# 30EC14-43EC14.net
KiCad netlist of a schematic drawn in EAGLE
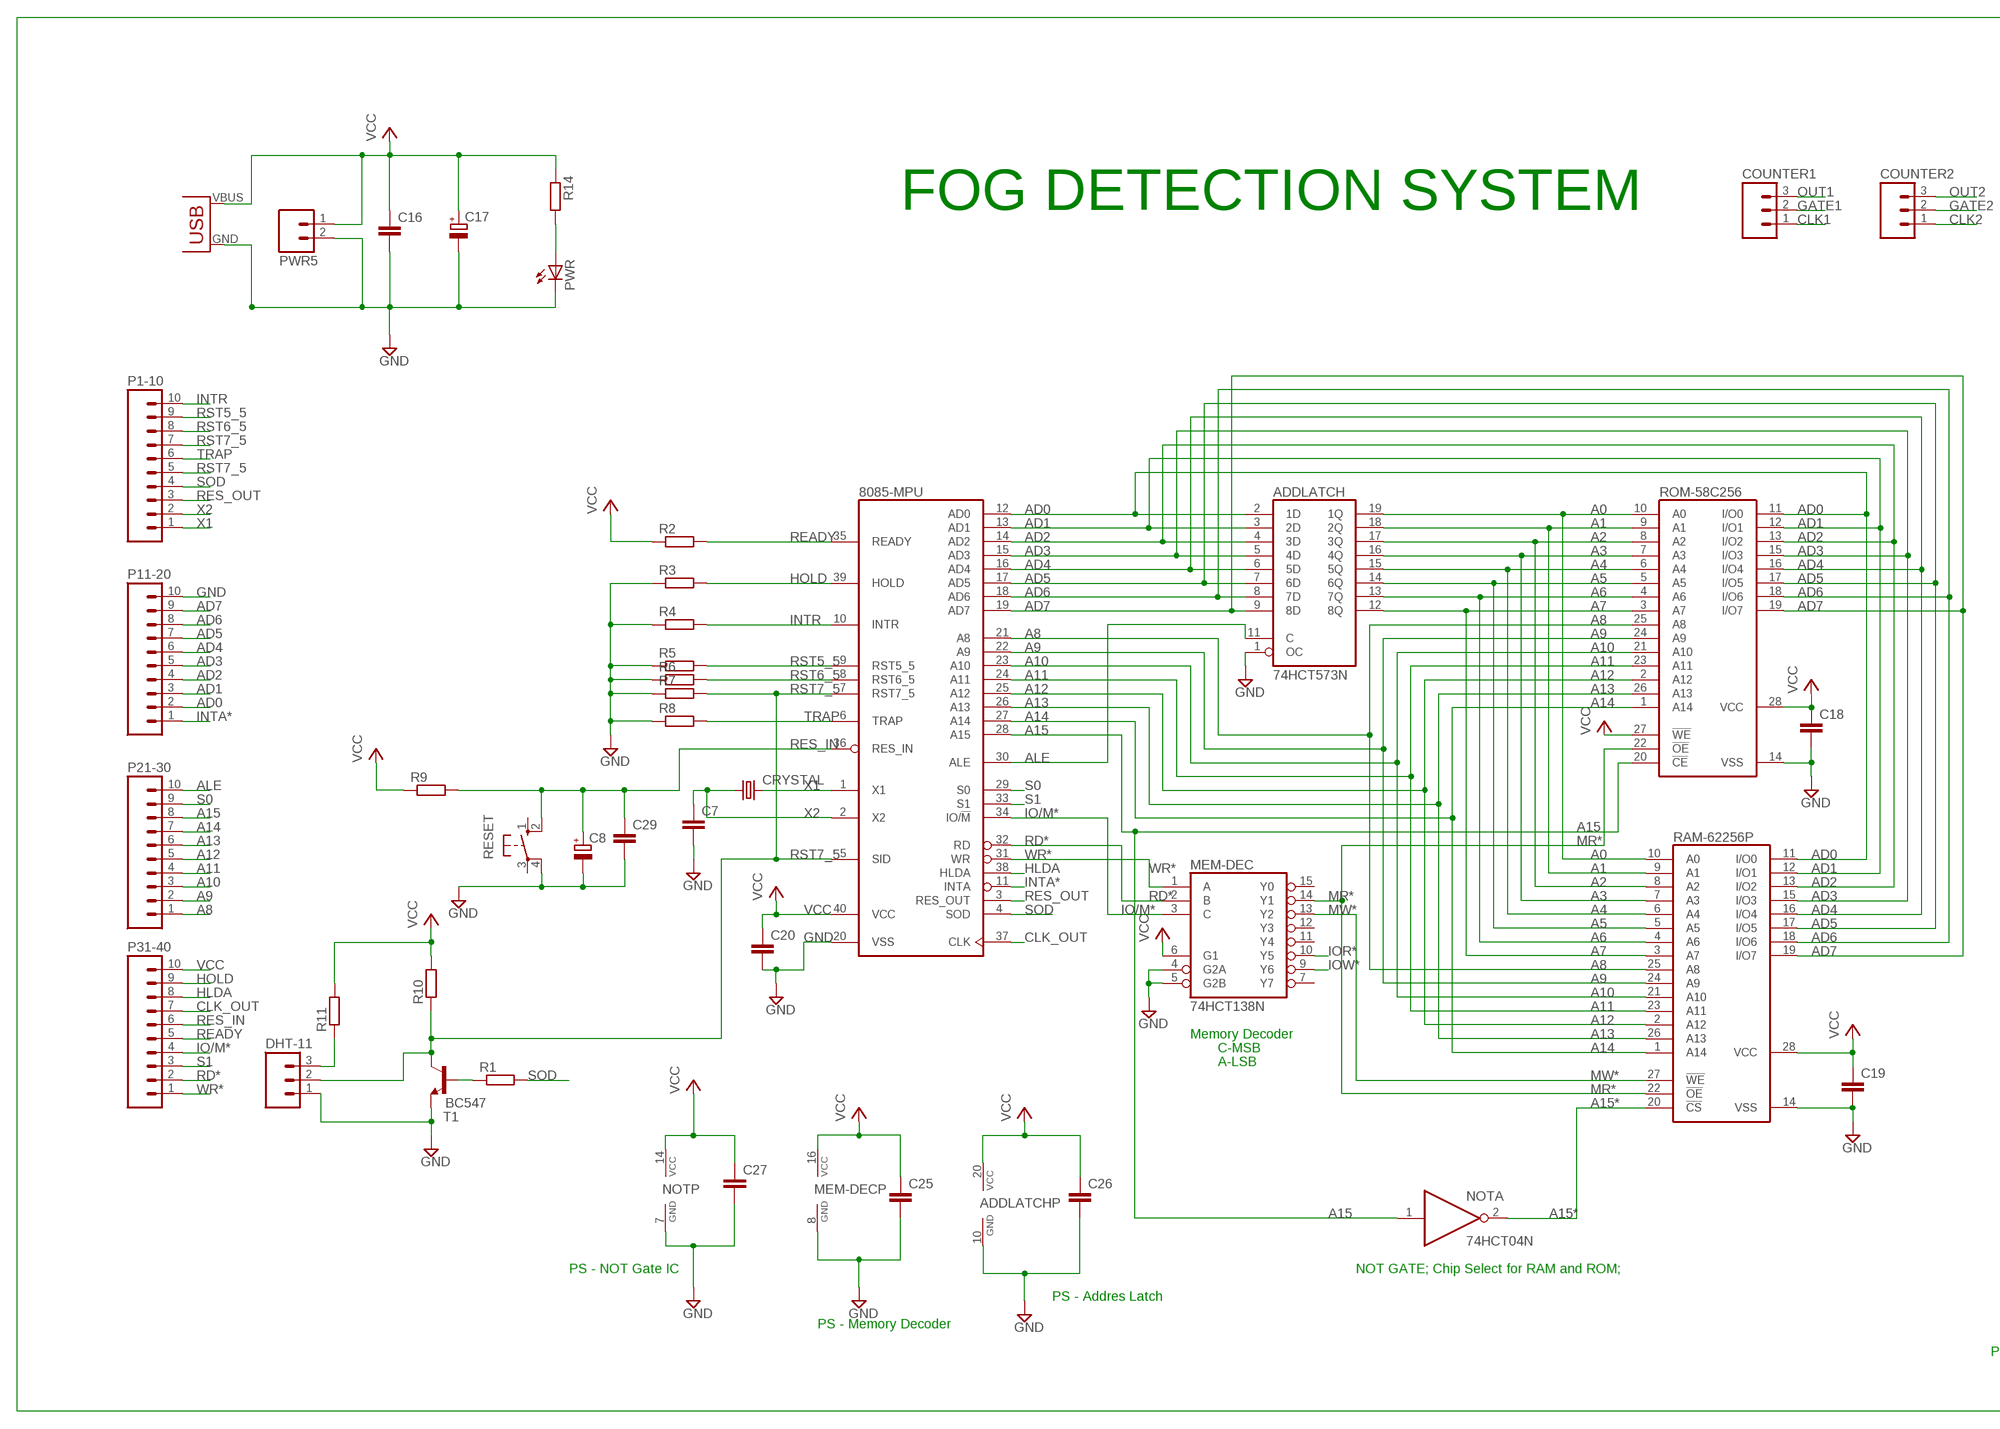
[diagram p0: schematic, sheet 1, part 1 of 2]
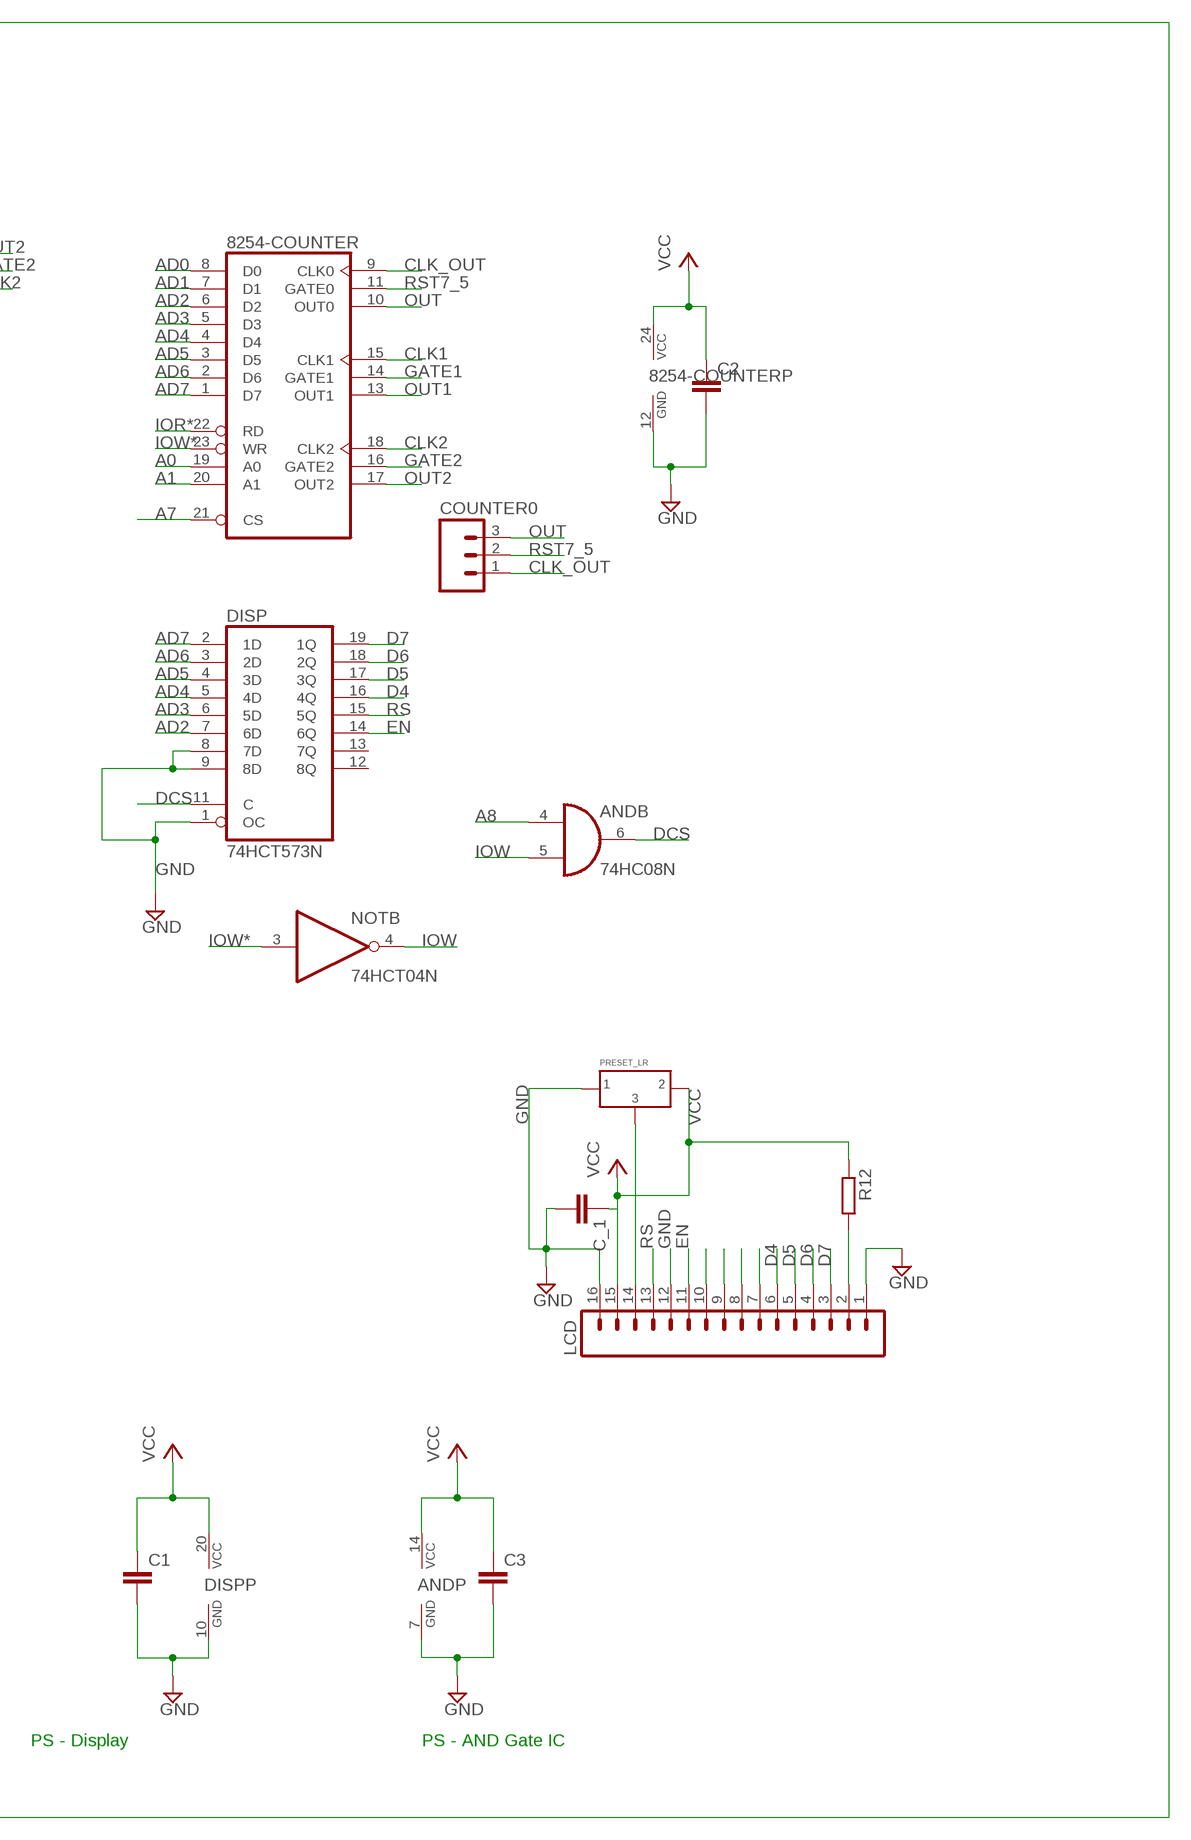
[diagram p1: schematic, sheet 1, part 2 of 2]

(export (version "E")
  (design (tool "Eeschema 10.0.6"))
  (components
    (comp (ref "8085-MPU")
      (value "8085")
      (footprint "eagle-import:DIL40")
      (libsource (lib "eagle-import") (part "8085"))
    )
    (comp (ref "8254-COUNTER")
      (value "8253")
      (footprint "eagle-import:DIL24-6")
      (libsource (lib "eagle-import") (part "8253"))
    )
    (comp (ref "ADDLATCH")
      (value "74HCT573N")
      (footprint "eagle-import:DIL20")
      (libsource (lib "eagle-import") (part "74573NHCT"))
    )
    (comp (ref "AND")
      (value "74HC08N")
      (footprint "eagle-import:DIL14")
      (libsource (lib "eagle-import") (part "7408NHC"))
    )
    (comp (ref "C1")
      (value "C-EU025-025X050")
      (footprint "eagle-import:C025-025X050")
      (libsource (lib "eagle-import") (part "resistor_C-EU025-025X050"))
    )
    (comp (ref "C2")
      (value "C-EU025-025X050")
      (footprint "eagle-import:C025-025X050")
      (libsource (lib "eagle-import") (part "C-EU025-025X050"))
    )
    (comp (ref "C3")
      (value "C-EU025-025X050")
      (footprint "eagle-import:C025-025X050")
      (libsource (lib "eagle-import") (part "resistor_C-EU025-025X050"))
    )
    (comp (ref "C7")
      (value "C-EU025-025X050")
      (footprint "eagle-import:C025-025X050")
      (libsource (lib "eagle-import") (part "C-EU025-025X050"))
    )
    (comp (ref "C8")
      (value "CPOL-EUE2.5-6")
      (footprint "eagle-import:E2,5-6")
      (libsource (lib "eagle-import") (part "CPOL-EUE2.5-6"))
    )
    (comp (ref "C16")
      (value "C-EU025-025X050")
      (footprint "eagle-import:C025-025X050")
      (libsource (lib "eagle-import") (part "resistor_C-EU025-025X050"))
    )
    (comp (ref "C17")
      (value "CPOL-EUE2.5-6")
      (footprint "eagle-import:E2,5-6")
      (libsource (lib "eagle-import") (part "CPOL-EUE2.5-6"))
    )
    (comp (ref "C18")
      (value "C-EU025-025X050")
      (footprint "eagle-import:C025-025X050")
      (libsource (lib "eagle-import") (part "resistor_C-EU025-025X050"))
    )
    (comp (ref "C19")
      (value "C-EU025-025X050")
      (footprint "eagle-import:C025-025X050")
      (libsource (lib "eagle-import") (part "resistor_C-EU025-025X050"))
    )
    (comp (ref "C20")
      (value "C-EU025-025X050")
      (footprint "eagle-import:C025-025X050")
      (libsource (lib "eagle-import") (part "resistor_C-EU025-025X050"))
    )
    (comp (ref "C25")
      (value "C-EU025-025X050")
      (footprint "eagle-import:C025-025X050")
      (libsource (lib "eagle-import") (part "resistor_C-EU025-025X050"))
    )
    (comp (ref "C26")
      (value "C-EU025-025X050")
      (footprint "eagle-import:C025-025X050")
      (libsource (lib "eagle-import") (part "resistor_C-EU025-025X050"))
    )
    (comp (ref "C27")
      (value "C-EU025-025X050")
      (footprint "eagle-import:C025-025X050")
      (libsource (lib "eagle-import") (part "resistor_C-EU025-025X050"))
    )
    (comp (ref "C29")
      (value "C-EU025-025X050")
      (footprint "eagle-import:C025-025X050")
      (libsource (lib "eagle-import") (part "C-EU025-025X050"))
    )
    (comp (ref "COUNTER0")
      (value "M03")
      (footprint "eagle-import:03P")
      (libsource (lib "eagle-import") (part "M03"))
    )
    (comp (ref "COUNTER1")
      (value "M03")
      (footprint "eagle-import:03P")
      (libsource (lib "eagle-import") (part "M03"))
    )
    (comp (ref "COUNTER2")
      (value "M03")
      (footprint "eagle-import:03P")
      (libsource (lib "eagle-import") (part "M03"))
    )
    (comp (ref "CRYSTAL")
      (value "CRYSTALHC49US")
      (footprint "eagle-import:HC49US")
      (libsource (lib "eagle-import") (part "CRYSTALHC49US"))
    )
    (comp (ref "C_1")
      (value "C-EU025-024X044")
      (footprint "eagle-import:C025-024X044")
      (libsource (lib "eagle-import") (part "C-EU025-024X044"))
    )
    (comp (ref "DHT-11")
      (value "M03")
      (footprint "eagle-import:03P")
      (libsource (lib "eagle-import") (part "M03"))
    )
    (comp (ref "DISP")
      (value "74HCT573N")
      (footprint "eagle-import:DIL20")
      (libsource (lib "eagle-import") (part "74573NHCT"))
    )
    (comp (ref "LCD")
      (value "M16")
      (footprint "eagle-import:16P")
      (libsource (lib "eagle-import") (part "M16"))
    )
    (comp (ref "MEM-DEC")
      (value "74HCT138N")
      (footprint "eagle-import:DIL16")
      (libsource (lib "eagle-import") (part "74138NHCT"))
    )
    (comp (ref "NOT")
      (value "74HCT04N")
      (footprint "eagle-import:DIL14")
      (libsource (lib "eagle-import") (part "7404NHCT"))
    )
    (comp (ref "P1-10")
      (value "M10")
      (footprint "eagle-import:10P")
      (libsource (lib "eagle-import") (part "M10"))
    )
    (comp (ref "P11-20")
      (value "M10")
      (footprint "eagle-import:10P")
      (libsource (lib "eagle-import") (part "M10"))
    )
    (comp (ref "P21-30")
      (value "M10")
      (footprint "eagle-import:10P")
      (libsource (lib "eagle-import") (part "M10"))
    )
    (comp (ref "P31-40")
      (value "M10")
      (footprint "eagle-import:10P")
      (libsource (lib "eagle-import") (part "M10"))
    )
    (comp (ref "PWR")
      (value "LED5MM")
      (footprint "eagle-import:LED5MM")
      (libsource (lib "eagle-import") (part "LED5MM"))
    )
    (comp (ref "PWR5")
      (value "M02")
      (footprint "eagle-import:02P")
      (libsource (lib "eagle-import") (part "M02"))
    )
    (comp (ref "R1")
      (value "R-EU_0204/7")
      (footprint "eagle-import:0204_7")
      (libsource (lib "eagle-import") (part "resistor_R-EU_0204/7"))
    )
    (comp (ref "R2")
      (value "R-EU_0204/7")
      (footprint "eagle-import:0204_7")
      (libsource (lib "eagle-import") (part "R-EU_0204/7"))
    )
    (comp (ref "R3")
      (value "R-EU_0204/7")
      (footprint "eagle-import:0204_7")
      (libsource (lib "eagle-import") (part "R-EU_0204/7"))
    )
    (comp (ref "R4")
      (value "R-EU_0204/7")
      (footprint "eagle-import:0204_7")
      (libsource (lib "eagle-import") (part "R-EU_0204/7"))
    )
    (comp (ref "R5")
      (value "R-EU_0204/7")
      (footprint "eagle-import:0204_7")
      (libsource (lib "eagle-import") (part "R-EU_0204/7"))
    )
    (comp (ref "R6")
      (value "R-EU_0204/7")
      (footprint "eagle-import:0204_7")
      (libsource (lib "eagle-import") (part "R-EU_0204/7"))
    )
    (comp (ref "R7")
      (value "R-EU_0204/7")
      (footprint "eagle-import:0204_7")
      (libsource (lib "eagle-import") (part "R-EU_0204/7"))
    )
    (comp (ref "R8")
      (value "R-EU_0204/7")
      (footprint "eagle-import:0204_7")
      (libsource (lib "eagle-import") (part "R-EU_0204/7"))
    )
    (comp (ref "R9")
      (value "R-EU_0204/7")
      (footprint "eagle-import:0204_7")
      (libsource (lib "eagle-import") (part "resistor_R-EU_0204/7"))
    )
    (comp (ref "R10")
      (value "R-EU_0204/7")
      (footprint "eagle-import:0204_7")
      (libsource (lib "eagle-import") (part "resistor_R-EU_0204/7"))
    )
    (comp (ref "R11")
      (value "R-EU_0204/7")
      (footprint "eagle-import:0204_7")
      (libsource (lib "eagle-import") (part "resistor_R-EU_0204/7"))
    )
    (comp (ref "R12")
      (value "R-EU_0204/7")
      (footprint "eagle-import:0204_7")
      (libsource (lib "eagle-import") (part "R-EU_0204/7"))
    )
    (comp (ref "R14")
      (value "R-EU_0204/7")
      (footprint "eagle-import:0204_7")
      (libsource (lib "eagle-import") (part "R-EU_0204/7"))
    )
    (comp (ref "RAM-62256P")
      (value "62256P")
      (footprint "eagle-import:DIL28-6")
      (libsource (lib "eagle-import") (part "62256P"))
    )
    (comp (ref "RESET")
      (value "10-XX")
      (footprint "eagle-import:B3F-10XX")
      (fields (field (name "MPN") "B3F-1000"))
      (libsource (lib "eagle-import") (part "10-XX"))
    )
    (comp (ref "ROM-58C256")
      (value "58C256P")
      (footprint "eagle-import:DIL28-6")
      (fields (field (name "MPN") "HN58C256AP85E"))
      (libsource (lib "eagle-import") (part "58C256P"))
    )
    (comp (ref "T1")
      (value "BC547")
      (footprint "eagle-import:TO92")
      (libsource (lib "eagle-import") (part "BC547"))
    )
    (comp (ref "U$1")
      (value "PRESET_LR")
      (footprint "eagle-import:PRESET_LR")
      (libsource (lib "eagle-import") (part "PRESET_LR"))
    )
    (comp (ref "USB")
      (value "USB(POWER)")
      (footprint "eagle-import:USB(POWER)")
      (libsource (lib "eagle-import") (part "USB(POWER)"))
    )
  )
  (nets
    (net (code "1") (name "/A0") (class "Default")
      (node (ref "8254-COUNTER") (pin "19") (pinfunction "A0_19") (pintype "input"))
      (node (ref "ADDLATCH") (pin "19") (pinfunction "1Q_19") (pintype "tri_state"))
      (node (ref "RAM-62256P") (pin "10") (pinfunction "A0_10") (pintype "input"))
      (node (ref "ROM-58C256") (pin "10") (pinfunction "A0_10") (pintype "input"))
    )
    (net (code "2") (name "/A1") (class "Default")
      (node (ref "8254-COUNTER") (pin "20") (pinfunction "A1_20") (pintype "input"))
      (node (ref "ADDLATCH") (pin "18") (pinfunction "2Q_18") (pintype "tri_state"))
      (node (ref "RAM-62256P") (pin "9") (pinfunction "A1_9") (pintype "input"))
      (node (ref "ROM-58C256") (pin "9") (pinfunction "A1_9") (pintype "input"))
    )
    (net (code "3") (name "/A2") (class "Default")
      (node (ref "ADDLATCH") (pin "17") (pinfunction "3Q_17") (pintype "tri_state"))
      (node (ref "RAM-62256P") (pin "8") (pinfunction "A2_8") (pintype "input"))
      (node (ref "ROM-58C256") (pin "8") (pinfunction "A2_8") (pintype "input"))
    )
    (net (code "4") (name "/A3") (class "Default")
      (node (ref "ADDLATCH") (pin "16") (pinfunction "4Q_16") (pintype "tri_state"))
      (node (ref "RAM-62256P") (pin "7") (pinfunction "A3_7") (pintype "input"))
      (node (ref "ROM-58C256") (pin "7") (pinfunction "A3_7") (pintype "input"))
    )
    (net (code "5") (name "/A4") (class "Default")
      (node (ref "ADDLATCH") (pin "15") (pinfunction "5Q_15") (pintype "tri_state"))
      (node (ref "RAM-62256P") (pin "6") (pinfunction "A4_6") (pintype "input"))
      (node (ref "ROM-58C256") (pin "6") (pinfunction "A4_6") (pintype "input"))
    )
    (net (code "6") (name "/A5") (class "Default")
      (node (ref "ADDLATCH") (pin "14") (pinfunction "6Q_14") (pintype "tri_state"))
      (node (ref "RAM-62256P") (pin "5") (pinfunction "A5_5") (pintype "input"))
      (node (ref "ROM-58C256") (pin "5") (pinfunction "A5_5") (pintype "input"))
    )
    (net (code "7") (name "/A6") (class "Default")
      (node (ref "ADDLATCH") (pin "13") (pinfunction "7Q_13") (pintype "tri_state"))
      (node (ref "RAM-62256P") (pin "4") (pinfunction "A6_4") (pintype "input"))
      (node (ref "ROM-58C256") (pin "4") (pinfunction "A6_4") (pintype "input"))
    )
    (net (code "8") (name "/A7") (class "Default")
      (node (ref "8254-COUNTER") (pin "21") (pinfunction "CS_21") (pintype "input"))
      (node (ref "ADDLATCH") (pin "12") (pinfunction "8Q_12") (pintype "tri_state"))
      (node (ref "RAM-62256P") (pin "3") (pinfunction "A7_3") (pintype "input"))
      (node (ref "ROM-58C256") (pin "3") (pinfunction "A7_3") (pintype "input"))
    )
    (net (code "9") (name "/A8") (class "Default")
      (node (ref "8085-MPU") (pin "21") (pinfunction "A8_21") (pintype "output"))
      (node (ref "AND") (pin "4") (pinfunction "I0_4") (pintype "input"))
      (node (ref "P21-30") (pin "1") (pinfunction "1_1") (pintype "passive"))
      (node (ref "RAM-62256P") (pin "25") (pinfunction "A8_25") (pintype "input"))
      (node (ref "ROM-58C256") (pin "25") (pinfunction "A8_25") (pintype "input"))
    )
    (net (code "10") (name "/A9") (class "Default")
      (node (ref "8085-MPU") (pin "22") (pinfunction "A9_22") (pintype "output"))
      (node (ref "P21-30") (pin "2") (pinfunction "2_2") (pintype "passive"))
      (node (ref "RAM-62256P") (pin "24") (pinfunction "A9_24") (pintype "input"))
      (node (ref "ROM-58C256") (pin "24") (pinfunction "A9_24") (pintype "input"))
    )
    (net (code "11") (name "/A10") (class "Default")
      (node (ref "8085-MPU") (pin "23") (pinfunction "A10_23") (pintype "output"))
      (node (ref "P21-30") (pin "3") (pinfunction "3_3") (pintype "passive"))
      (node (ref "RAM-62256P") (pin "21") (pinfunction "A10_21") (pintype "input"))
      (node (ref "ROM-58C256") (pin "21") (pinfunction "A10_21") (pintype "input"))
    )
    (net (code "12") (name "/A11") (class "Default")
      (node (ref "8085-MPU") (pin "24") (pinfunction "A11_24") (pintype "output"))
      (node (ref "P21-30") (pin "4") (pinfunction "4_4") (pintype "passive"))
      (node (ref "RAM-62256P") (pin "23") (pinfunction "A11_23") (pintype "input"))
      (node (ref "ROM-58C256") (pin "23") (pinfunction "A11_23") (pintype "input"))
    )
    (net (code "13") (name "/A12") (class "Default")
      (node (ref "8085-MPU") (pin "25") (pinfunction "A12_25") (pintype "output"))
      (node (ref "P21-30") (pin "5") (pinfunction "5_5") (pintype "passive"))
      (node (ref "RAM-62256P") (pin "2") (pinfunction "A12_2") (pintype "input"))
      (node (ref "ROM-58C256") (pin "2") (pinfunction "A12_2") (pintype "input"))
    )
    (net (code "14") (name "/A13") (class "Default")
      (node (ref "8085-MPU") (pin "26") (pinfunction "A13_26") (pintype "output"))
      (node (ref "P21-30") (pin "6") (pinfunction "6_6") (pintype "passive"))
      (node (ref "RAM-62256P") (pin "26") (pinfunction "A13_26") (pintype "input"))
      (node (ref "ROM-58C256") (pin "26") (pinfunction "A13_26") (pintype "input"))
    )
    (net (code "15") (name "/A14") (class "Default")
      (node (ref "8085-MPU") (pin "27") (pinfunction "A14_27") (pintype "output"))
      (node (ref "P21-30") (pin "7") (pinfunction "7_7") (pintype "passive"))
      (node (ref "RAM-62256P") (pin "1") (pinfunction "A14_1") (pintype "input"))
      (node (ref "ROM-58C256") (pin "1") (pinfunction "A14_1") (pintype "input"))
    )
    (net (code "16") (name "/A15") (class "Default")
      (node (ref "8085-MPU") (pin "28") (pinfunction "A15_28") (pintype "output"))
      (node (ref "NOT") (pin "1") (pinfunction "I_1") (pintype "input"))
      (node (ref "P21-30") (pin "8") (pinfunction "8_8") (pintype "passive"))
      (node (ref "ROM-58C256") (pin "20") (pinfunction "~{CE}_20") (pintype "input"))
    )
    (net (code "17") (name "/A15*") (class "Default")
      (node (ref "NOT") (pin "2") (pinfunction "O_2") (pintype "output"))
      (node (ref "RAM-62256P") (pin "20") (pinfunction "~{CS}_20") (pintype "input"))
    )
    (net (code "18") (name "/AD0") (class "Default")
      (node (ref "8085-MPU") (pin "12") (pinfunction "AD0_12") (pintype "bidirectional"))
      (node (ref "8254-COUNTER") (pin "8") (pinfunction "D0_8") (pintype "bidirectional"))
      (node (ref "ADDLATCH") (pin "2") (pinfunction "1D_2") (pintype "input"))
      (node (ref "P11-20") (pin "2") (pinfunction "2_2") (pintype "passive"))
      (node (ref "RAM-62256P") (pin "11") (pinfunction "I/O0_11") (pintype "bidirectional"))
      (node (ref "ROM-58C256") (pin "11") (pinfunction "I/O0_11") (pintype "tri_state"))
    )
    (net (code "19") (name "/AD1") (class "Default")
      (node (ref "8085-MPU") (pin "13") (pinfunction "AD1_13") (pintype "bidirectional"))
      (node (ref "8254-COUNTER") (pin "7") (pinfunction "D1_7") (pintype "bidirectional"))
      (node (ref "ADDLATCH") (pin "3") (pinfunction "2D_3") (pintype "input"))
      (node (ref "P11-20") (pin "3") (pinfunction "3_3") (pintype "passive"))
      (node (ref "RAM-62256P") (pin "12") (pinfunction "I/O1_12") (pintype "bidirectional"))
      (node (ref "ROM-58C256") (pin "12") (pinfunction "I/O1_12") (pintype "tri_state"))
    )
    (net (code "20") (name "/AD2") (class "Default")
      (node (ref "8085-MPU") (pin "14") (pinfunction "AD2_14") (pintype "bidirectional"))
      (node (ref "8254-COUNTER") (pin "6") (pinfunction "D2_6") (pintype "bidirectional"))
      (node (ref "ADDLATCH") (pin "4") (pinfunction "3D_4") (pintype "input"))
      (node (ref "DISP") (pin "7") (pinfunction "6D_7") (pintype "input"))
      (node (ref "P11-20") (pin "4") (pinfunction "4_4") (pintype "passive"))
      (node (ref "RAM-62256P") (pin "13") (pinfunction "I/O2_13") (pintype "bidirectional"))
      (node (ref "ROM-58C256") (pin "13") (pinfunction "I/O2_13") (pintype "tri_state"))
    )
    (net (code "21") (name "/AD3") (class "Default")
      (node (ref "8085-MPU") (pin "15") (pinfunction "AD3_15") (pintype "bidirectional"))
      (node (ref "8254-COUNTER") (pin "5") (pinfunction "D3_5") (pintype "bidirectional"))
      (node (ref "ADDLATCH") (pin "5") (pinfunction "4D_5") (pintype "input"))
      (node (ref "DISP") (pin "6") (pinfunction "5D_6") (pintype "input"))
      (node (ref "P11-20") (pin "5") (pinfunction "5_5") (pintype "passive"))
      (node (ref "RAM-62256P") (pin "15") (pinfunction "I/O3_15") (pintype "bidirectional"))
      (node (ref "ROM-58C256") (pin "15") (pinfunction "I/O3_15") (pintype "tri_state"))
    )
    (net (code "22") (name "/AD4") (class "Default")
      (node (ref "8085-MPU") (pin "16") (pinfunction "AD4_16") (pintype "bidirectional"))
      (node (ref "8254-COUNTER") (pin "4") (pinfunction "D4_4") (pintype "bidirectional"))
      (node (ref "ADDLATCH") (pin "6") (pinfunction "5D_6") (pintype "input"))
      (node (ref "DISP") (pin "5") (pinfunction "4D_5") (pintype "input"))
      (node (ref "P11-20") (pin "6") (pinfunction "6_6") (pintype "passive"))
      (node (ref "RAM-62256P") (pin "16") (pinfunction "I/O4_16") (pintype "bidirectional"))
      (node (ref "ROM-58C256") (pin "16") (pinfunction "I/O4_16") (pintype "tri_state"))
    )
    (net (code "23") (name "/AD5") (class "Default")
      (node (ref "8085-MPU") (pin "17") (pinfunction "AD5_17") (pintype "bidirectional"))
      (node (ref "8254-COUNTER") (pin "3") (pinfunction "D5_3") (pintype "bidirectional"))
      (node (ref "ADDLATCH") (pin "7") (pinfunction "6D_7") (pintype "input"))
      (node (ref "DISP") (pin "4") (pinfunction "3D_4") (pintype "input"))
      (node (ref "P11-20") (pin "7") (pinfunction "7_7") (pintype "passive"))
      (node (ref "RAM-62256P") (pin "17") (pinfunction "I/O5_17") (pintype "bidirectional"))
      (node (ref "ROM-58C256") (pin "17") (pinfunction "I/O5_17") (pintype "tri_state"))
    )
    (net (code "24") (name "/AD6") (class "Default")
      (node (ref "8085-MPU") (pin "18") (pinfunction "AD6_18") (pintype "bidirectional"))
      (node (ref "8254-COUNTER") (pin "2") (pinfunction "D6_2") (pintype "bidirectional"))
      (node (ref "ADDLATCH") (pin "8") (pinfunction "7D_8") (pintype "input"))
      (node (ref "DISP") (pin "3") (pinfunction "2D_3") (pintype "input"))
      (node (ref "P11-20") (pin "8") (pinfunction "8_8") (pintype "passive"))
      (node (ref "RAM-62256P") (pin "18") (pinfunction "I/O6_18") (pintype "bidirectional"))
      (node (ref "ROM-58C256") (pin "18") (pinfunction "I/O6_18") (pintype "tri_state"))
    )
    (net (code "25") (name "/AD7") (class "Default")
      (node (ref "8085-MPU") (pin "19") (pinfunction "AD7_19") (pintype "bidirectional"))
      (node (ref "8254-COUNTER") (pin "1") (pinfunction "D7_1") (pintype "bidirectional"))
      (node (ref "ADDLATCH") (pin "9") (pinfunction "8D_9") (pintype "input"))
      (node (ref "DISP") (pin "2") (pinfunction "1D_2") (pintype "input"))
      (node (ref "P11-20") (pin "9") (pinfunction "9_9") (pintype "passive"))
      (node (ref "RAM-62256P") (pin "19") (pinfunction "I/O7_19") (pintype "bidirectional"))
      (node (ref "ROM-58C256") (pin "19") (pinfunction "I/O7_19") (pintype "tri_state"))
    )
    (net (code "26") (name "/ALE") (class "Default")
      (node (ref "8085-MPU") (pin "30") (pinfunction "ALE_30") (pintype "output"))
      (node (ref "ADDLATCH") (pin "11") (pinfunction "C_11") (pintype "input"))
      (node (ref "P21-30") (pin "10") (pinfunction "10_10") (pintype "passive"))
    )
    (net (code "27") (name "/CLK1") (class "Default")
      (node (ref "8254-COUNTER") (pin "15") (pinfunction "CLK1_15") (pintype "input"))
      (node (ref "COUNTER1") (pin "1") (pinfunction "1_1") (pintype "passive"))
    )
    (net (code "28") (name "/CLK2") (class "Default")
      (node (ref "8254-COUNTER") (pin "18") (pinfunction "CLK2_18") (pintype "input"))
      (node (ref "COUNTER2") (pin "1") (pinfunction "1_1") (pintype "passive"))
    )
    (net (code "29") (name "/CLK_OUT") (class "Default")
      (node (ref "8085-MPU") (pin "37") (pinfunction "CLK_37") (pintype "output"))
      (node (ref "8254-COUNTER") (pin "9") (pinfunction "CLK0_9") (pintype "input"))
      (node (ref "COUNTER0") (pin "1") (pinfunction "1_1") (pintype "passive"))
      (node (ref "P31-40") (pin "7") (pinfunction "7_7") (pintype "passive"))
    )
    (net (code "30") (name "/D4") (class "Default")
      (node (ref "DISP") (pin "16") (pinfunction "4Q_16") (pintype "tri_state"))
      (node (ref "LCD") (pin "6") (pinfunction "6_6") (pintype "passive"))
    )
    (net (code "31") (name "/D5") (class "Default")
      (node (ref "DISP") (pin "17") (pinfunction "3Q_17") (pintype "tri_state"))
      (node (ref "LCD") (pin "5") (pinfunction "5_5") (pintype "passive"))
    )
    (net (code "32") (name "/D6") (class "Default")
      (node (ref "DISP") (pin "18") (pinfunction "2Q_18") (pintype "tri_state"))
      (node (ref "LCD") (pin "4") (pinfunction "4_4") (pintype "passive"))
    )
    (net (code "33") (name "/D7") (class "Default")
      (node (ref "DISP") (pin "19") (pinfunction "1Q_19") (pintype "tri_state"))
      (node (ref "LCD") (pin "3") (pinfunction "3_3") (pintype "passive"))
    )
    (net (code "34") (name "/DCS") (class "Default")
      (node (ref "AND") (pin "6") (pinfunction "O_6") (pintype "output"))
      (node (ref "DISP") (pin "11") (pinfunction "C_11") (pintype "input"))
    )
    (net (code "35") (name "/EN") (class "Default")
      (node (ref "DISP") (pin "14") (pinfunction "6Q_14") (pintype "tri_state"))
      (node (ref "LCD") (pin "11") (pinfunction "11_11") (pintype "passive"))
    )
    (net (code "36") (name "/GATE1") (class "Default")
      (node (ref "8254-COUNTER") (pin "14") (pinfunction "GATE1_14") (pintype "input"))
      (node (ref "COUNTER1") (pin "2") (pinfunction "2_2") (pintype "passive"))
    )
    (net (code "37") (name "/GATE2") (class "Default")
      (node (ref "8254-COUNTER") (pin "16") (pinfunction "GATE2_16") (pintype "input"))
      (node (ref "COUNTER2") (pin "2") (pinfunction "2_2") (pintype "passive"))
    )
    (net (code "38") (name "/HLDA") (class "Default")
      (node (ref "8085-MPU") (pin "38") (pinfunction "HLDA_38") (pintype "output"))
      (node (ref "P31-40") (pin "8") (pinfunction "8_8") (pintype "passive"))
    )
    (net (code "39") (name "/HOLD") (class "Default")
      (node (ref "8085-MPU") (pin "39") (pinfunction "HOLD_39") (pintype "input"))
      (node (ref "P31-40") (pin "9") (pinfunction "9_9") (pintype "passive"))
      (node (ref "R3") (pin "2") (pinfunction "2_2") (pintype "passive"))
    )
    (net (code "40") (name "/INTA*") (class "Default")
      (node (ref "8085-MPU") (pin "11") (pinfunction "INTA_11") (pintype "output"))
      (node (ref "P11-20") (pin "1") (pinfunction "1_1") (pintype "passive"))
    )
    (net (code "41") (name "/INTR") (class "Default")
      (node (ref "8085-MPU") (pin "10") (pinfunction "INTR_10") (pintype "input"))
      (node (ref "P1-10") (pin "10") (pinfunction "10_10") (pintype "passive"))
      (node (ref "R4") (pin "2") (pinfunction "2_2") (pintype "passive"))
    )
    (net (code "42") (name "/IOR*") (class "Default")
      (node (ref "8254-COUNTER") (pin "22") (pinfunction "RD_22") (pintype "input"))
      (node (ref "MEM-DEC") (pin "10") (pinfunction "Y5_10") (pintype "output"))
    )
    (net (code "43") (name "/IOW") (class "Default")
      (node (ref "AND") (pin "5") (pinfunction "I1_5") (pintype "input"))
      (node (ref "NOT") (pin "4") (pinfunction "O_4") (pintype "output"))
    )
    (net (code "44") (name "/IOW*") (class "Default")
      (node (ref "8254-COUNTER") (pin "23") (pinfunction "WR_23") (pintype "input"))
      (node (ref "MEM-DEC") (pin "9") (pinfunction "Y6_9") (pintype "output"))
      (node (ref "NOT") (pin "3") (pinfunction "I_3") (pintype "input"))
    )
    (net (code "45") (name "/IO{slash}M*") (class "Default")
      (node (ref "8085-MPU") (pin "34") (pinfunction "IO/~{M}_34") (pintype "output"))
      (node (ref "MEM-DEC") (pin "3") (pinfunction "C_3") (pintype "input"))
      (node (ref "P31-40") (pin "4") (pinfunction "4_4") (pintype "passive"))
    )
    (net (code "46") (name "/MR*") (class "Default")
      (node (ref "MEM-DEC") (pin "14") (pinfunction "Y1_14") (pintype "output"))
      (node (ref "RAM-62256P") (pin "22") (pinfunction "~{OE}_22") (pintype "input"))
      (node (ref "ROM-58C256") (pin "22") (pinfunction "~{OE}_22") (pintype "input"))
    )
    (net (code "47") (name "/MW*") (class "Default")
      (node (ref "MEM-DEC") (pin "13") (pinfunction "Y2_13") (pintype "output"))
      (node (ref "RAM-62256P") (pin "27") (pinfunction "~{WE}_27") (pintype "input"))
    )
    (net (code "48") (name "/OUT") (class "Default")
      (node (ref "8254-COUNTER") (pin "10") (pinfunction "OUT0_10") (pintype "output"))
      (node (ref "COUNTER0") (pin "3") (pinfunction "3_3") (pintype "passive"))
    )
    (net (code "49") (name "/OUT1") (class "Default")
      (node (ref "8254-COUNTER") (pin "13") (pinfunction "OUT1_13") (pintype "output"))
      (node (ref "COUNTER1") (pin "3") (pinfunction "3_3") (pintype "passive"))
    )
    (net (code "50") (name "/OUT2") (class "Default")
      (node (ref "8254-COUNTER") (pin "17") (pinfunction "OUT2_17") (pintype "output"))
      (node (ref "COUNTER2") (pin "3") (pinfunction "3_3") (pintype "passive"))
    )
    (net (code "51") (name "/RD*") (class "Default")
      (node (ref "8085-MPU") (pin "32") (pinfunction "RD_32") (pintype "output"))
      (node (ref "MEM-DEC") (pin "2") (pinfunction "B_2") (pintype "input"))
      (node (ref "P31-40") (pin "2") (pinfunction "2_2") (pintype "passive"))
    )
    (net (code "52") (name "/READY") (class "Default")
      (node (ref "8085-MPU") (pin "35") (pinfunction "READY_35") (pintype "input"))
      (node (ref "P31-40") (pin "5") (pinfunction "5_5") (pintype "passive"))
      (node (ref "R2") (pin "2") (pinfunction "2_2") (pintype "passive"))
    )
    (net (code "53") (name "/RES_IN") (class "Default")
      (node (ref "8085-MPU") (pin "36") (pinfunction "RES_IN_36") (pintype "input"))
      (node (ref "C29") (pin "1") (pinfunction "1_1") (pintype "passive"))
      (node (ref "C8") (pin "+") (pinfunction "+_+") (pintype "passive"))
      (node (ref "P31-40") (pin "6") (pinfunction "6_6") (pintype "passive"))
      (node (ref "R9") (pin "2") (pinfunction "2_2") (pintype "passive"))
      (node (ref "RESET") (pin "2") (pinfunction "S1_2") (pintype "passive"))
    )
    (net (code "54") (name "/RES_OUT") (class "Default")
      (node (ref "8085-MPU") (pin "3") (pinfunction "RES_OUT_3") (pintype "output"))
      (node (ref "P1-10") (pin "3") (pinfunction "3_3") (pintype "passive"))
    )
    (net (code "55") (name "/RS") (class "Default")
      (node (ref "DISP") (pin "15") (pinfunction "5Q_15") (pintype "tri_state"))
      (node (ref "LCD") (pin "13") (pinfunction "13_13") (pintype "passive"))
    )
    (net (code "56") (name "/RST5_5") (class "Default")
      (node (ref "8085-MPU") (pin "9") (pinfunction "RST5_5_9") (pintype "input"))
      (node (ref "P1-10") (pin "9") (pinfunction "9_9") (pintype "passive"))
      (node (ref "R5") (pin "2") (pinfunction "2_2") (pintype "passive"))
    )
    (net (code "57") (name "/RST6_5") (class "Default")
      (node (ref "8085-MPU") (pin "8") (pinfunction "RST6_5_8") (pintype "input"))
      (node (ref "P1-10") (pin "8") (pinfunction "8_8") (pintype "passive"))
      (node (ref "R6") (pin "2") (pinfunction "2_2") (pintype "passive"))
    )
    (net (code "58") (name "/RST7_5") (class "Default")
      (node (ref "8085-MPU") (pin "5") (pinfunction "SID_5") (pintype "input"))
      (node (ref "8085-MPU") (pin "7") (pinfunction "RST7_5_7") (pintype "input"))
      (node (ref "8254-COUNTER") (pin "11") (pinfunction "GATE0_11") (pintype "input"))
      (node (ref "COUNTER0") (pin "2") (pinfunction "2_2") (pintype "passive"))
      (node (ref "DHT-11") (pin "2") (pinfunction "2_2") (pintype "passive"))
      (node (ref "P1-10") (pin "5") (pinfunction "5_5") (pintype "passive"))
      (node (ref "P1-10") (pin "7") (pinfunction "7_7") (pintype "passive"))
      (node (ref "R10") (pin "1") (pinfunction "1_1") (pintype "passive"))
      (node (ref "R7") (pin "2") (pinfunction "2_2") (pintype "passive"))
      (node (ref "T1") (pin "3") (pinfunction "C_3") (pintype "passive"))
    )
    (net (code "59") (name "/S0") (class "Default")
      (node (ref "8085-MPU") (pin "29") (pinfunction "S0_29") (pintype "output"))
      (node (ref "P21-30") (pin "9") (pinfunction "9_9") (pintype "passive"))
    )
    (net (code "60") (name "/S1") (class "Default")
      (node (ref "8085-MPU") (pin "33") (pinfunction "S1_33") (pintype "output"))
      (node (ref "P31-40") (pin "3") (pinfunction "3_3") (pintype "passive"))
    )
    (net (code "61") (name "/SOD") (class "Default")
      (node (ref "8085-MPU") (pin "4") (pinfunction "SOD_4") (pintype "output"))
      (node (ref "P1-10") (pin "4") (pinfunction "4_4") (pintype "passive"))
      (node (ref "R1") (pin "2") (pinfunction "2_2") (pintype "passive"))
    )
    (net (code "62") (name "/TRAP") (class "Default")
      (node (ref "8085-MPU") (pin "6") (pinfunction "TRAP_6") (pintype "input"))
      (node (ref "P1-10") (pin "6") (pinfunction "6_6") (pintype "passive"))
      (node (ref "R8") (pin "2") (pinfunction "2_2") (pintype "passive"))
    )
    (net (code "63") (name "/WR*") (class "Default")
      (node (ref "8085-MPU") (pin "31") (pinfunction "WR_31") (pintype "output"))
      (node (ref "MEM-DEC") (pin "1") (pinfunction "A_1") (pintype "input"))
      (node (ref "P31-40") (pin "1") (pinfunction "1_1") (pintype "passive"))
    )
    (net (code "64") (name "/X1") (class "Default")
      (node (ref "8085-MPU") (pin "1") (pinfunction "X1_1") (pintype "input"))
      (node (ref "CRYSTAL") (pin "2") (pinfunction "2_2") (pintype "passive"))
      (node (ref "P1-10") (pin "1") (pinfunction "1_1") (pintype "passive"))
    )
    (net (code "65") (name "/X2") (class "Default")
      (node (ref "8085-MPU") (pin "2") (pinfunction "X2_2") (pintype "input"))
      (node (ref "C7") (pin "1") (pinfunction "1_1") (pintype "passive"))
      (node (ref "CRYSTAL") (pin "1") (pinfunction "1_1") (pintype "passive"))
      (node (ref "P1-10") (pin "2") (pinfunction "2_2") (pintype "passive"))
    )
    (net (code "66") (name "GND") (class "Default")
      (node (ref "8085-MPU") (pin "20") (pinfunction "VSS_20") (pintype "power_in"))
      (node (ref "8254-COUNTER") (pin "12") (pinfunction "GND_12") (pintype "power_in"))
      (node (ref "ADDLATCH") (pin "1") (pinfunction "OC_1") (pintype "input"))
      (node (ref "ADDLATCH") (pin "10") (pinfunction "GND_10") (pintype "power_in"))
      (node (ref "AND") (pin "7") (pinfunction "GND_7") (pintype "power_in"))
      (node (ref "C1") (pin "2") (pinfunction "2_2") (pintype "passive"))
      (node (ref "C16") (pin "2") (pinfunction "2_2") (pintype "passive"))
      (node (ref "C17") (pin "-") (pinfunction "-_-") (pintype "passive"))
      (node (ref "C18") (pin "2") (pinfunction "2_2") (pintype "passive"))
      (node (ref "C19") (pin "2") (pinfunction "2_2") (pintype "passive"))
      (node (ref "C2") (pin "2") (pinfunction "2_2") (pintype "passive"))
      (node (ref "C20") (pin "2") (pinfunction "2_2") (pintype "passive"))
      (node (ref "C25") (pin "2") (pinfunction "2_2") (pintype "passive"))
      (node (ref "C26") (pin "2") (pinfunction "2_2") (pintype "passive"))
      (node (ref "C27") (pin "2") (pinfunction "2_2") (pintype "passive"))
      (node (ref "C29") (pin "2") (pinfunction "2_2") (pintype "passive"))
      (node (ref "C3") (pin "2") (pinfunction "2_2") (pintype "passive"))
      (node (ref "C7") (pin "2") (pinfunction "2_2") (pintype "passive"))
      (node (ref "C8") (pin "-") (pinfunction "-_-") (pintype "passive"))
      (node (ref "C_1") (pin "2") (pinfunction "2_2") (pintype "passive"))
      (node (ref "DHT-11") (pin "1") (pinfunction "1_1") (pintype "passive"))
      (node (ref "DISP") (pin "1") (pinfunction "OC_1") (pintype "input"))
      (node (ref "DISP") (pin "10") (pinfunction "GND_10") (pintype "power_in"))
      (node (ref "DISP") (pin "8") (pinfunction "7D_8") (pintype "input"))
      (node (ref "DISP") (pin "9") (pinfunction "8D_9") (pintype "input"))
      (node (ref "LCD") (pin "1") (pinfunction "1_1") (pintype "passive"))
      (node (ref "LCD") (pin "12") (pinfunction "12_12") (pintype "passive"))
      (node (ref "LCD") (pin "16") (pinfunction "16_16") (pintype "passive"))
      (node (ref "MEM-DEC") (pin "4") (pinfunction "G2A_4") (pintype "input"))
      (node (ref "MEM-DEC") (pin "5") (pinfunction "G2B_5") (pintype "input"))
      (node (ref "MEM-DEC") (pin "8") (pinfunction "GND_8") (pintype "power_in"))
      (node (ref "NOT") (pin "7") (pinfunction "GND_7") (pintype "power_in"))
      (node (ref "P11-20") (pin "10") (pinfunction "10_10") (pintype "passive"))
      (node (ref "PWR") (pin "K") (pinfunction "C_K") (pintype "passive"))
      (node (ref "PWR5") (pin "2") (pinfunction "2_2") (pintype "passive"))
      (node (ref "R3") (pin "1") (pinfunction "1_1") (pintype "passive"))
      (node (ref "R4") (pin "1") (pinfunction "1_1") (pintype "passive"))
      (node (ref "R5") (pin "1") (pinfunction "1_1") (pintype "passive"))
      (node (ref "R6") (pin "1") (pinfunction "1_1") (pintype "passive"))
      (node (ref "R7") (pin "1") (pinfunction "1_1") (pintype "passive"))
      (node (ref "R8") (pin "1") (pinfunction "1_1") (pintype "passive"))
      (node (ref "RAM-62256P") (pin "14") (pinfunction "VSS_14") (pintype "power_in"))
      (node (ref "RESET") (pin "4") (pinfunction "P1_4") (pintype "passive"))
      (node (ref "ROM-58C256") (pin "14") (pinfunction "VSS_14") (pintype "power_in"))
      (node (ref "T1") (pin "1") (pinfunction "E_1") (pintype "passive"))
      (node (ref "U$1") (pin "P$1") (pinfunction "1_P$1") (pintype "passive"))
      (node (ref "USB") (pin "GND") (pinfunction "GND_GND") (pintype "power_in"))
    )
    (net (code "67") (name "Net-(DHT-11-Pad3)") (class "Default")
      (node (ref "DHT-11") (pin "3") (pinfunction "3_3") (pintype "passive"))
      (node (ref "R11") (pin "1") (pinfunction "1_1") (pintype "passive"))
    )
    (net (code "68") (name "Net-(LCD-Pad2)") (class "Default")
      (node (ref "LCD") (pin "2") (pinfunction "2_2") (pintype "passive"))
      (node (ref "R12") (pin "2") (pinfunction "2_2") (pintype "passive"))
    )
    (net (code "69") (name "Net-(PWR-PadA)") (class "Default")
      (node (ref "PWR") (pin "A") (pinfunction "A_A") (pintype "passive"))
      (node (ref "R14") (pin "2") (pinfunction "2_2") (pintype "passive"))
    )
    (net (code "70") (name "Net-(T1-B)") (class "Default")
      (node (ref "R1") (pin "1") (pinfunction "1_1") (pintype "passive"))
      (node (ref "T1") (pin "2") (pinfunction "B_2") (pintype "passive"))
    )
    (net (code "71") (name "Net-(U$1-3)") (class "Default")
      (node (ref "LCD") (pin "14") (pinfunction "14_14") (pintype "passive"))
      (node (ref "U$1") (pin "P$3") (pinfunction "3_P$3") (pintype "passive"))
    )
    (net (code "72") (name "VCC") (class "Default")
      (node (ref "8085-MPU") (pin "40") (pinfunction "VCC_40") (pintype "power_in"))
      (node (ref "8254-COUNTER") (pin "24") (pinfunction "VCC_24") (pintype "power_in"))
      (node (ref "ADDLATCH") (pin "20") (pinfunction "VCC_20") (pintype "power_in"))
      (node (ref "AND") (pin "14") (pinfunction "VCC_14") (pintype "power_in"))
      (node (ref "C1") (pin "1") (pinfunction "1_1") (pintype "passive"))
      (node (ref "C16") (pin "1") (pinfunction "1_1") (pintype "passive"))
      (node (ref "C17") (pin "+") (pinfunction "+_+") (pintype "passive"))
      (node (ref "C18") (pin "1") (pinfunction "1_1") (pintype "passive"))
      (node (ref "C19") (pin "1") (pinfunction "1_1") (pintype "passive"))
      (node (ref "C2") (pin "1") (pinfunction "1_1") (pintype "passive"))
      (node (ref "C20") (pin "1") (pinfunction "1_1") (pintype "passive"))
      (node (ref "C25") (pin "1") (pinfunction "1_1") (pintype "passive"))
      (node (ref "C26") (pin "1") (pinfunction "1_1") (pintype "passive"))
      (node (ref "C27") (pin "1") (pinfunction "1_1") (pintype "passive"))
      (node (ref "C3") (pin "1") (pinfunction "1_1") (pintype "passive"))
      (node (ref "C_1") (pin "1") (pinfunction "1_1") (pintype "passive"))
      (node (ref "DISP") (pin "20") (pinfunction "VCC_20") (pintype "power_in"))
      (node (ref "LCD") (pin "15") (pinfunction "15_15") (pintype "passive"))
      (node (ref "MEM-DEC") (pin "16") (pinfunction "VCC_16") (pintype "power_in"))
      (node (ref "MEM-DEC") (pin "6") (pinfunction "G1_6") (pintype "input"))
      (node (ref "NOT") (pin "14") (pinfunction "VCC_14") (pintype "power_in"))
      (node (ref "P31-40") (pin "10") (pinfunction "10_10") (pintype "passive"))
      (node (ref "PWR5") (pin "1") (pinfunction "1_1") (pintype "passive"))
      (node (ref "R10") (pin "2") (pinfunction "2_2") (pintype "passive"))
      (node (ref "R11") (pin "2") (pinfunction "2_2") (pintype "passive"))
      (node (ref "R12") (pin "1") (pinfunction "1_1") (pintype "passive"))
      (node (ref "R14") (pin "1") (pinfunction "1_1") (pintype "passive"))
      (node (ref "R2") (pin "1") (pinfunction "1_1") (pintype "passive"))
      (node (ref "R9") (pin "1") (pinfunction "1_1") (pintype "passive"))
      (node (ref "RAM-62256P") (pin "28") (pinfunction "VCC_28") (pintype "power_in"))
      (node (ref "ROM-58C256") (pin "27") (pinfunction "~{WE}_27") (pintype "input"))
      (node (ref "ROM-58C256") (pin "28") (pinfunction "VCC_28") (pintype "power_in"))
      (node (ref "U$1") (pin "P$2") (pinfunction "2_P$2") (pintype "passive"))
      (node (ref "USB") (pin "VBUS") (pinfunction "VCC_VBUS") (pintype "power_in"))
    )
    (net (code "73") (name "unconnected-(DISPA-7Q-Pad13)") (class "Default")
      (node (ref "DISP") (pin "13") (pinfunction "7Q_13") (pintype "tri_state"))
    )
    (net (code "74") (name "unconnected-(DISPA-8Q-Pad12)") (class "Default")
      (node (ref "DISP") (pin "12") (pinfunction "8Q_12") (pintype "tri_state"))
    )
    (net (code "75") (name "unconnected-(LCD-Pad7)") (class "Default")
      (node (ref "LCD") (pin "7") (pinfunction "7_7") (pintype "passive"))
    )
    (net (code "76") (name "unconnected-(LCD-Pad8)") (class "Default")
      (node (ref "LCD") (pin "8") (pinfunction "8_8") (pintype "passive"))
    )
    (net (code "77") (name "unconnected-(LCD-Pad9)") (class "Default")
      (node (ref "LCD") (pin "9") (pinfunction "9_9") (pintype "passive"))
    )
    (net (code "78") (name "unconnected-(LCD-Pad10)") (class "Default")
      (node (ref "LCD") (pin "10") (pinfunction "10_10") (pintype "passive"))
    )
    (net (code "79") (name "unconnected-(MEM-DECA-Y0-Pad15)") (class "Default")
      (node (ref "MEM-DEC") (pin "15") (pinfunction "Y0_15") (pintype "output"))
    )
    (net (code "80") (name "unconnected-(MEM-DECA-Y3-Pad12)") (class "Default")
      (node (ref "MEM-DEC") (pin "12") (pinfunction "Y3_12") (pintype "output"))
    )
    (net (code "81") (name "unconnected-(MEM-DECA-Y4-Pad11)") (class "Default")
      (node (ref "MEM-DEC") (pin "11") (pinfunction "Y4_11") (pintype "output"))
    )
    (net (code "82") (name "unconnected-(MEM-DECA-Y7-Pad7)") (class "Default")
      (node (ref "MEM-DEC") (pin "7") (pinfunction "Y7_7") (pintype "output"))
    )
    (net (code "83") (name "unconnected-(RESET-P-Pad3)") (class "Default")
      (node (ref "RESET") (pin "3") (pinfunction "P_3") (pintype "passive"))
    )
    (net (code "84") (name "unconnected-(RESET-S-Pad1)") (class "Default")
      (node (ref "RESET") (pin "1") (pinfunction "S_1") (pintype "passive"))
    )
  )
)
